# M515C.net
KiCad netlist of a schematic drawn in EAGLE
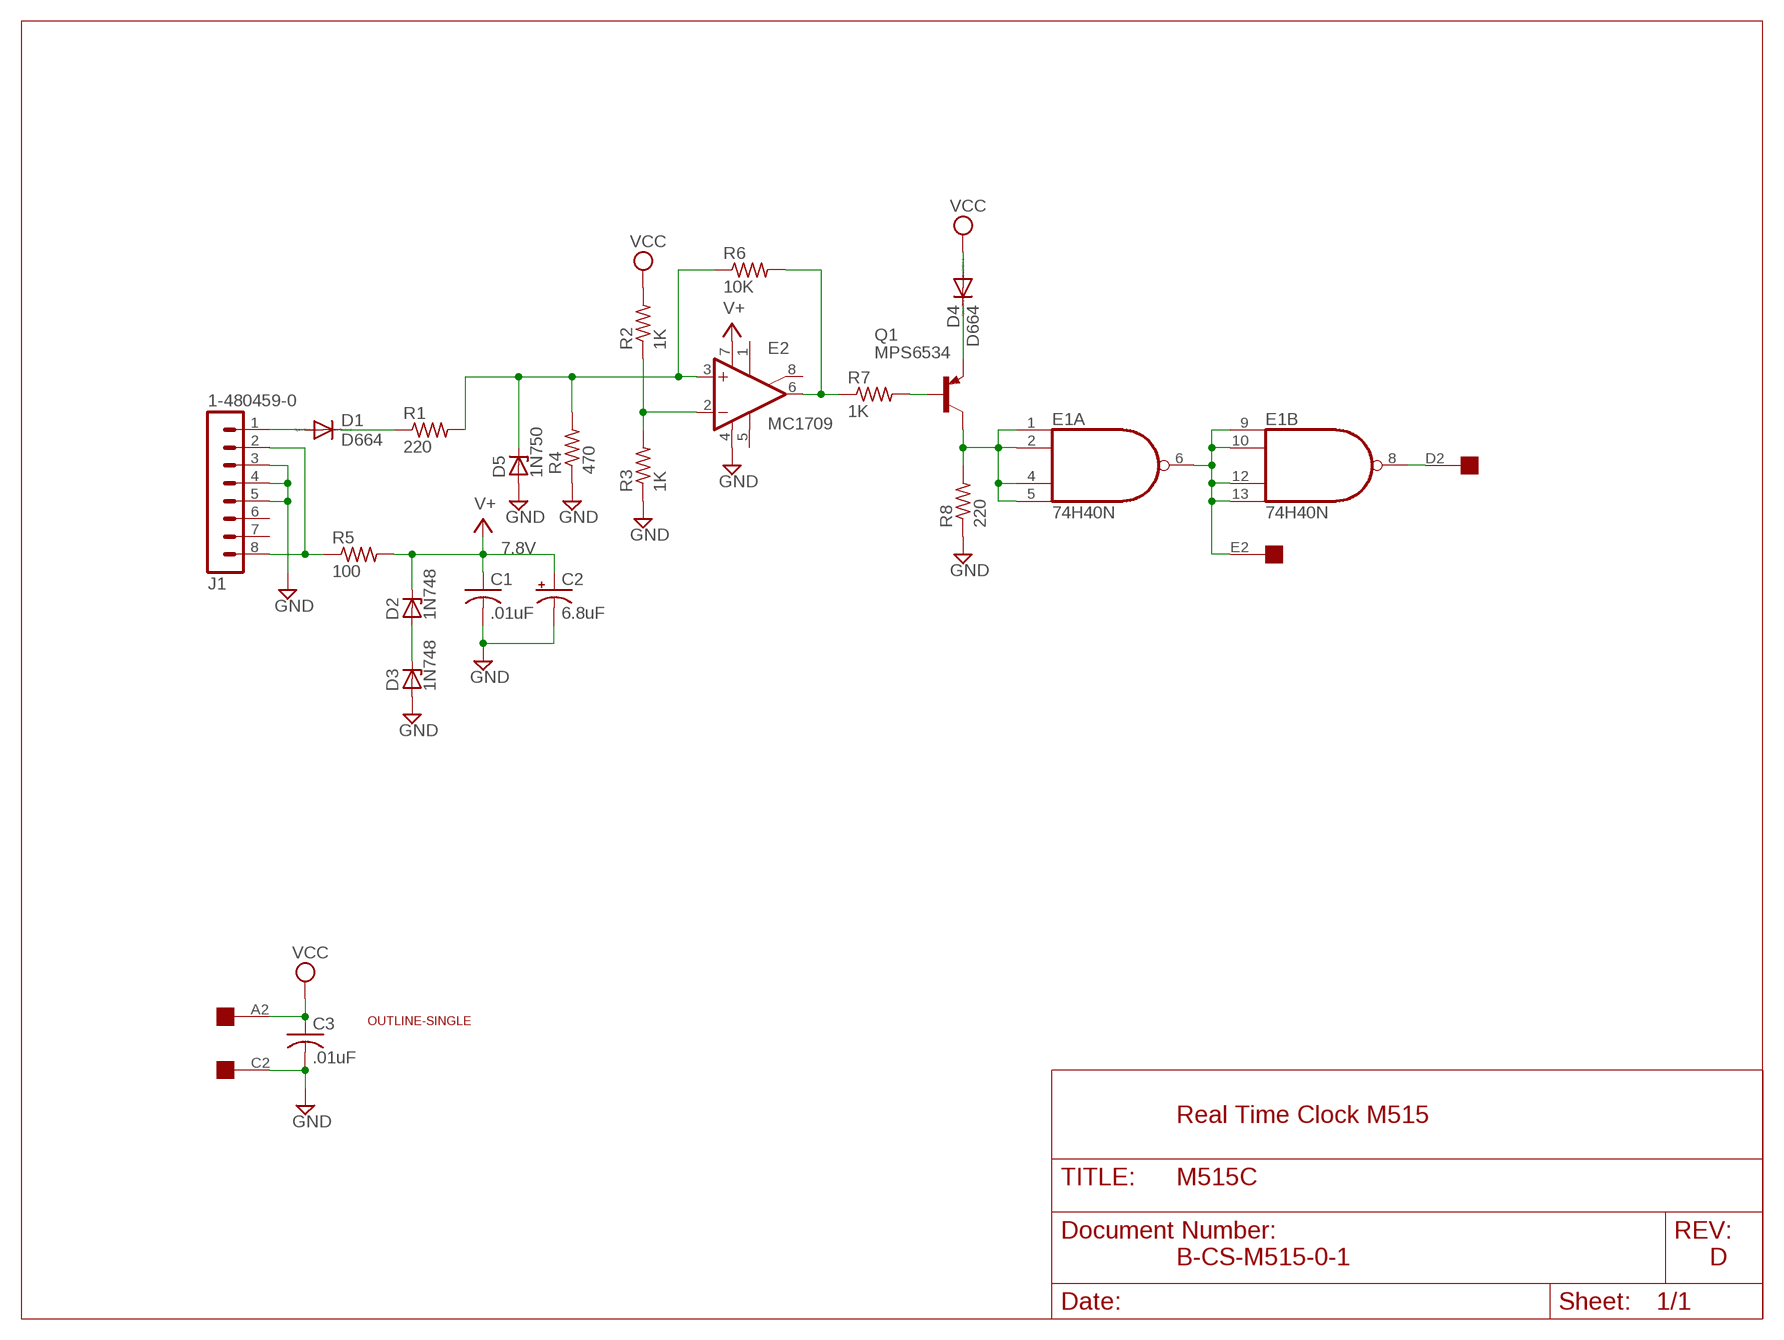
[diagram p0: schematic, sheet 1]

(export (version "E")
  (design (tool "Eeschema 10.0.6"))
  (components
    (comp (ref "C1")
      (value ".01uF")
      (footprint "eagle-import:C050-025X075")
      (libsource (lib "eagle-import") (part "C-US050-025X075"))
    )
    (comp (ref "C2")
      (value "6.8uF")
      (footprint "eagle-import:E12-8")
      (libsource (lib "eagle-import") (part "CPOL-USE20-8AXIAL"))
    )
    (comp (ref "C3")
      (value ".01uF")
      (footprint "eagle-import:C050-025X075")
      (libsource (lib "eagle-import") (part "C-US050-025X075"))
    )
    (comp (ref "D1")
      (value "D664")
      (footprint "eagle-import:DO35-10")
      (libsource (lib "eagle-import") (part "DIODE-DO35-10"))
    )
    (comp (ref "D2")
      (value "1N748")
      (footprint "eagle-import:DO35Z10")
      (libsource (lib "eagle-import") (part "ZENER-DIODEDO35Z10"))
    )
    (comp (ref "D3")
      (value "1N748")
      (footprint "eagle-import:DO35Z10")
      (libsource (lib "eagle-import") (part "ZENER-DIODEDO35Z10"))
    )
    (comp (ref "D4")
      (value "D664")
      (footprint "eagle-import:DO35-10")
      (libsource (lib "eagle-import") (part "DIODE-DO35-10"))
    )
    (comp (ref "D5")
      (value "1N750")
      (footprint "eagle-import:DO35Z10")
      (libsource (lib "eagle-import") (part "ZENER-DIODEDO35Z10"))
    )
    (comp (ref "E1")
      (value "74H40N")
      (footprint "eagle-import:DIL14")
      (libsource (lib "eagle-import") (part "7440NS"))
    )
    (comp (ref "E2")
      (value "MC1709")
      (footprint "eagle-import:H08C")
      (libsource (lib "eagle-import") (part "MC1709"))
    )
    (comp (ref "J1")
      (value "1-480459-0")
      (footprint "eagle-import:1-480459-0")
      (libsource (lib "eagle-import") (part "1-480459-0"))
    )
    (comp (ref "Q1")
      (value "MPS6534")
      (footprint "eagle-import:TO5")
      (libsource (lib "eagle-import") (part "-PNP-TO5"))
    )
    (comp (ref "R1")
      (value "220")
      (footprint "eagle-import:0207_10")
      (libsource (lib "eagle-import") (part "R-US_0207/10"))
    )
    (comp (ref "R2")
      (value "1K")
      (footprint "eagle-import:0207_10")
      (libsource (lib "eagle-import") (part "R-US_0207/10"))
    )
    (comp (ref "R3")
      (value "1K")
      (footprint "eagle-import:0207_10")
      (libsource (lib "eagle-import") (part "R-US_0207/10"))
    )
    (comp (ref "R4")
      (value "470")
      (footprint "eagle-import:0207_10")
      (libsource (lib "eagle-import") (part "R-US_0207/10"))
    )
    (comp (ref "R5")
      (value "100")
      (footprint "eagle-import:0207_10")
      (libsource (lib "eagle-import") (part "R-US_0207/10"))
    )
    (comp (ref "R6")
      (value "10K")
      (footprint "eagle-import:0207_10")
      (libsource (lib "eagle-import") (part "R-US_0207/10"))
    )
    (comp (ref "R7")
      (value "1K")
      (footprint "eagle-import:0207_10")
      (libsource (lib "eagle-import") (part "R-US_0207/10"))
    )
    (comp (ref "R8")
      (value "220")
      (footprint "eagle-import:0207_10")
      (libsource (lib "eagle-import") (part "R-US_0207/10"))
    )
    (comp (ref "U$1")
      (value "OUTLINE-SINGLE")
      (footprint "eagle-import:SINGLE")
      (libsource (lib "eagle-import") (part "OUTLINE-SINGLE"))
    )
    (comp (ref "U$3")
      (value "EDGE-1")
      (footprint "eagle-import:EDGE-CON1")
      (libsource (lib "eagle-import") (part "EDGE-1"))
    )
  )
  (nets
    (net (code "1") (name "GND") (class "Default")
      (node (ref "C1") (pin "2") (pinfunction "2_2") (pintype "passive"))
      (node (ref "C2") (pin "-") (pinfunction "-_-") (pintype "passive"))
      (node (ref "C3") (pin "2") (pinfunction "2_2") (pintype "passive"))
      (node (ref "D3") (pin "A") (pinfunction "A_A") (pintype "passive"))
      (node (ref "D5") (pin "A") (pinfunction "A_A") (pintype "passive"))
      (node (ref "E2") (pin "4") (pinfunction "V-_4") (pintype "power_in"))
      (node (ref "J1") (pin "3") (pinfunction "3_3") (pintype "passive"))
      (node (ref "J1") (pin "4") (pinfunction "4_4") (pintype "passive"))
      (node (ref "J1") (pin "5") (pinfunction "5_5") (pintype "passive"))
      (node (ref "R3") (pin "1") (pinfunction "1_1") (pintype "passive"))
      (node (ref "R4") (pin "1") (pinfunction "1_1") (pintype "passive"))
      (node (ref "R8") (pin "1") (pinfunction "1_1") (pintype "passive"))
      (node (ref "U$3") (pin "C2") (pinfunction "1_C2") (pintype "bidirectional"))
    )
    (net (code "2") (name "Net-(D1-PadA)") (class "Default")
      (node (ref "D1") (pin "A") (pinfunction "A_A") (pintype "passive"))
      (node (ref "J1") (pin "1") (pinfunction "1_1") (pintype "passive"))
    )
    (net (code "3") (name "Net-(D1-PadC)") (class "Default")
      (node (ref "D1") (pin "C") (pinfunction "C_C") (pintype "passive"))
      (node (ref "R1") (pin "1") (pinfunction "1_1") (pintype "passive"))
    )
    (net (code "4") (name "Net-(D2-PadA)") (class "Default")
      (node (ref "D2") (pin "A") (pinfunction "A_A") (pintype "passive"))
      (node (ref "D3") (pin "C") (pinfunction "C_C") (pintype "passive"))
    )
    (net (code "5") (name "Net-(E1C-I0)") (class "Default")
      (node (ref "E1") (pin "1") (pinfunction "I0_1") (pintype "input"))
      (node (ref "E1") (pin "2") (pinfunction "I1_2") (pintype "input"))
      (node (ref "E1") (pin "4") (pinfunction "I2_4") (pintype "input"))
      (node (ref "E1") (pin "5") (pinfunction "I3_5") (pintype "input"))
      (node (ref "Q1") (pin "3") (pinfunction "C_3") (pintype "passive"))
      (node (ref "R8") (pin "2") (pinfunction "2_2") (pintype "passive"))
    )
    (net (code "6") (name "Net-(E1C-O)") (class "Default")
      (node (ref "E1") (pin "10") (pinfunction "I1_10") (pintype "input"))
      (node (ref "E1") (pin "12") (pinfunction "I2_12") (pintype "input"))
      (node (ref "E1") (pin "13") (pinfunction "I3_13") (pintype "input"))
      (node (ref "E1") (pin "6") (pinfunction "O_6") (pintype "output"))
      (node (ref "E1") (pin "9") (pinfunction "I0_9") (pintype "input"))
      (node (ref "U$3") (pin "E2") (pinfunction "1_E2") (pintype "bidirectional"))
    )
    (net (code "7") (name "Net-(E1D-O)") (class "Default")
      (node (ref "E1") (pin "8") (pinfunction "O_8") (pintype "output"))
      (node (ref "U$3") (pin "D2") (pinfunction "1_D2") (pintype "bidirectional"))
    )
    (net (code "8") (name "Net-(E2-+IN)") (class "Default")
      (node (ref "D5") (pin "C") (pinfunction "C_C") (pintype "passive"))
      (node (ref "E2") (pin "3") (pinfunction "+IN_3") (pintype "input"))
      (node (ref "R1") (pin "2") (pinfunction "2_2") (pintype "passive"))
      (node (ref "R4") (pin "2") (pinfunction "2_2") (pintype "passive"))
      (node (ref "R6") (pin "1") (pinfunction "1_1") (pintype "passive"))
    )
    (net (code "9") (name "Net-(E2--IN)") (class "Default")
      (node (ref "E2") (pin "2") (pinfunction "-IN_2") (pintype "input"))
      (node (ref "R2") (pin "1") (pinfunction "1_1") (pintype "passive"))
      (node (ref "R3") (pin "2") (pinfunction "2_2") (pintype "passive"))
    )
    (net (code "10") (name "Net-(E2-OUT)") (class "Default")
      (node (ref "E2") (pin "6") (pinfunction "OUT_6") (pintype "output"))
      (node (ref "R6") (pin "2") (pinfunction "2_2") (pintype "passive"))
      (node (ref "R7") (pin "1") (pinfunction "1_1") (pintype "passive"))
    )
    (net (code "11") (name "Net-(J1-Pad2)") (class "Default")
      (node (ref "J1") (pin "2") (pinfunction "2_2") (pintype "passive"))
      (node (ref "J1") (pin "8") (pinfunction "8_8") (pintype "passive"))
      (node (ref "R5") (pin "1") (pinfunction "1_1") (pintype "passive"))
    )
    (net (code "12") (name "Net-(Q1-B)") (class "Default")
      (node (ref "Q1") (pin "2") (pinfunction "B_2") (pintype "passive"))
      (node (ref "R7") (pin "2") (pinfunction "2_2") (pintype "passive"))
    )
    (net (code "13") (name "Net-(Q1-E)") (class "Default")
      (node (ref "D4") (pin "C") (pinfunction "C_C") (pintype "passive"))
      (node (ref "Q1") (pin "1") (pinfunction "E_1") (pintype "passive"))
    )
    (net (code "14") (name "V+") (class "Default")
      (node (ref "C1") (pin "1") (pinfunction "1_1") (pintype "passive"))
      (node (ref "C2") (pin "+") (pinfunction "+_+") (pintype "passive"))
      (node (ref "D2") (pin "C") (pinfunction "C_C") (pintype "passive"))
      (node (ref "E2") (pin "7") (pinfunction "V+_7") (pintype "power_in"))
      (node (ref "R5") (pin "2") (pinfunction "2_2") (pintype "passive"))
    )
    (net (code "15") (name "VCC") (class "Default")
      (node (ref "C3") (pin "1") (pinfunction "1_1") (pintype "passive"))
      (node (ref "D4") (pin "A") (pinfunction "A_A") (pintype "passive"))
      (node (ref "R2") (pin "2") (pinfunction "2_2") (pintype "passive"))
      (node (ref "U$3") (pin "A2") (pinfunction "1_A2") (pintype "bidirectional"))
    )
    (net (code "16") (name "unconnected-(E2-ON1-Pad1)") (class "Default")
      (node (ref "E2") (pin "1") (pinfunction "ON1_1") (pintype "passive"))
    )
    (net (code "17") (name "unconnected-(E2-ON2-Pad8)") (class "Default")
      (node (ref "E2") (pin "8") (pinfunction "ON2_8") (pintype "passive"))
    )
    (net (code "18") (name "unconnected-(E2-OPT-Pad5)") (class "Default")
      (node (ref "E2") (pin "5") (pinfunction "OPT_5") (pintype "passive"))
    )
    (net (code "19") (name "unconnected-(J1-Pad6)") (class "Default")
      (node (ref "J1") (pin "6") (pinfunction "6_6") (pintype "passive"))
    )
    (net (code "20") (name "unconnected-(J1-Pad7)") (class "Default")
      (node (ref "J1") (pin "7") (pinfunction "7_7") (pintype "passive"))
    )
  )
)
